# ParralelLEDStrip.net
KiCad netlist of a schematic drawn in Altium Designer
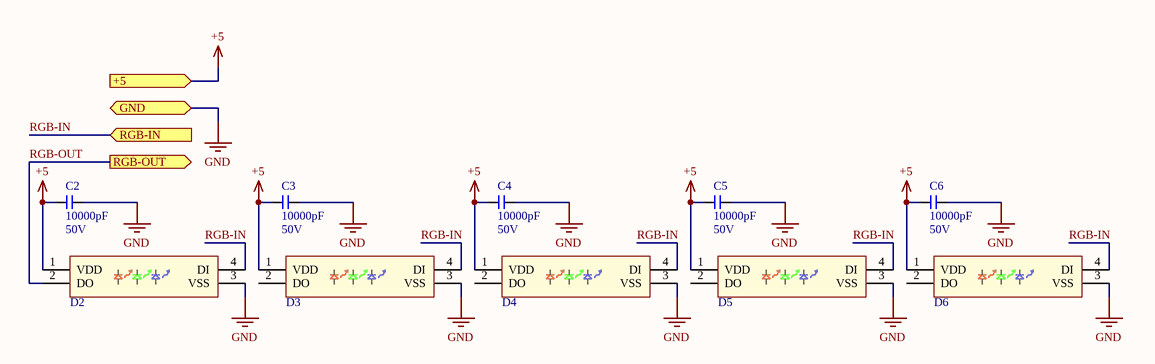
[diagram p0: ParralelLEDStrip.SchDoc]

(export (version "E")
  (design (tool "Eeschema 10.0.6"))
  (components
    (comp (ref "C2")
      (value "__template_cap")
      (footprint "C0805")
      (fields
        (field (name "CAPACITANCE (SHORTHAND)") "10000pF")
        (field (name "RATED VOLTAGE") "50V")
        (field (name "MANUFACTURER") "Murata Electronics North America")
      )
      (libsource (lib "passives") (part "__template_cap"))
    )
    (comp (ref "C3")
      (value "__template_cap")
      (footprint "C0805")
      (fields
        (field (name "CAPACITANCE (SHORTHAND)") "10000pF")
        (field (name "RATED VOLTAGE") "50V")
        (field (name "MANUFACTURER") "Murata Electronics North America")
      )
      (libsource (lib "passives") (part "__template_cap"))
    )
    (comp (ref "C4")
      (value "__template_cap")
      (footprint "C0805")
      (fields
        (field (name "CAPACITANCE (SHORTHAND)") "10000pF")
        (field (name "RATED VOLTAGE") "50V")
        (field (name "MANUFACTURER") "Murata Electronics North America")
      )
      (libsource (lib "passives") (part "__template_cap"))
    )
    (comp (ref "C5")
      (value "__template_cap")
      (footprint "C0805")
      (fields
        (field (name "CAPACITANCE (SHORTHAND)") "10000pF")
        (field (name "RATED VOLTAGE") "50V")
        (field (name "MANUFACTURER") "Murata Electronics North America")
      )
      (libsource (lib "passives") (part "__template_cap"))
    )
    (comp (ref "C6")
      (value "__template_cap")
      (footprint "C0805")
      (fields
        (field (name "CAPACITANCE (SHORTHAND)") "10000pF")
        (field (name "RATED VOLTAGE") "50V")
        (field (name "MANUFACTURER") "Murata Electronics North America")
      )
      (libsource (lib "passives") (part "__template_cap"))
    )
    (comp (ref "D2")
      (value "LED_WS2812B")
      (footprint "4DFN5X5_WGS2812B")
      (description "LED RGB WS2812B")
      (libsource (lib "SSI") (part "LED_WS2812B"))
    )
    (comp (ref "D3")
      (value "LED_WS2812B")
      (footprint "4DFN5X5_WGS2812B")
      (description "LED RGB WS2812B")
      (libsource (lib "SSI") (part "LED_WS2812B"))
    )
    (comp (ref "D4")
      (value "LED_WS2812B")
      (footprint "4DFN5X5_WGS2812B")
      (description "LED RGB WS2812B")
      (libsource (lib "SSI") (part "LED_WS2812B"))
    )
    (comp (ref "D5")
      (value "LED_WS2812B")
      (footprint "4DFN5X5_WGS2812B")
      (description "LED RGB WS2812B")
      (libsource (lib "SSI") (part "LED_WS2812B"))
    )
    (comp (ref "D6")
      (value "LED_WS2812B")
      (footprint "4DFN5X5_WGS2812B")
      (description "LED RGB WS2812B")
      (libsource (lib "SSI") (part "LED_WS2812B"))
    )
  )
  (nets
    (net (code "1") (name "+5") (class "Default")
      (node (ref "C2") (pin "1") (pintype "passive"))
      (node (ref "C3") (pin "1") (pintype "passive"))
      (node (ref "C4") (pin "1") (pintype "passive"))
      (node (ref "C5") (pin "1") (pintype "passive"))
      (node (ref "C6") (pin "1") (pintype "passive"))
      (node (ref "D2") (pin "1") (pinfunction "VDD_1") (pintype "passive"))
      (node (ref "D3") (pin "1") (pinfunction "VDD_1") (pintype "passive"))
      (node (ref "D4") (pin "1") (pinfunction "VDD_1") (pintype "passive"))
      (node (ref "D5") (pin "1") (pinfunction "VDD_1") (pintype "passive"))
      (node (ref "D6") (pin "1") (pinfunction "VDD_1") (pintype "passive"))
    )
    (net (code "2") (name "/RGB-IN") (class "Default")
      (node (ref "D2") (pin "4") (pinfunction "DI_4") (pintype "passive"))
      (node (ref "D3") (pin "4") (pinfunction "DI_4") (pintype "passive"))
      (node (ref "D4") (pin "4") (pinfunction "DI_4") (pintype "passive"))
      (node (ref "D5") (pin "4") (pinfunction "DI_4") (pintype "passive"))
      (node (ref "D6") (pin "4") (pinfunction "DI_4") (pintype "passive"))
    )
    (net (code "3") (name "/RGB-OUT") (class "Default")
      (node (ref "D2") (pin "2") (pinfunction "DO_2") (pintype "passive"))
    )
    (net (code "4") (name "GND") (class "Default")
      (node (ref "C2") (pin "2") (pintype "passive"))
      (node (ref "C3") (pin "2") (pintype "passive"))
      (node (ref "C4") (pin "2") (pintype "passive"))
      (node (ref "C5") (pin "2") (pintype "passive"))
      (node (ref "C6") (pin "2") (pintype "passive"))
      (node (ref "D2") (pin "3") (pinfunction "VSS_3") (pintype "passive"))
      (node (ref "D3") (pin "3") (pinfunction "VSS_3") (pintype "passive"))
      (node (ref "D4") (pin "3") (pinfunction "VSS_3") (pintype "passive"))
      (node (ref "D5") (pin "3") (pinfunction "VSS_3") (pintype "passive"))
      (node (ref "D6") (pin "3") (pinfunction "VSS_3") (pintype "passive"))
    )
    (net (code "5") (name "unconnected-(D3-DO-Pad2)") (class "Default")
      (node (ref "D3") (pin "2") (pinfunction "DO_2") (pintype "passive"))
    )
    (net (code "6") (name "unconnected-(D4-DO-Pad2)") (class "Default")
      (node (ref "D4") (pin "2") (pinfunction "DO_2") (pintype "passive"))
    )
    (net (code "7") (name "unconnected-(D5-DO-Pad2)") (class "Default")
      (node (ref "D5") (pin "2") (pinfunction "DO_2") (pintype "passive"))
    )
    (net (code "8") (name "unconnected-(D6-DO-Pad2)") (class "Default")
      (node (ref "D6") (pin "2") (pinfunction "DO_2") (pintype "passive"))
    )
  )
)
